# Multiplexers.net
KiCad netlist of a schematic drawn in Altium Designer
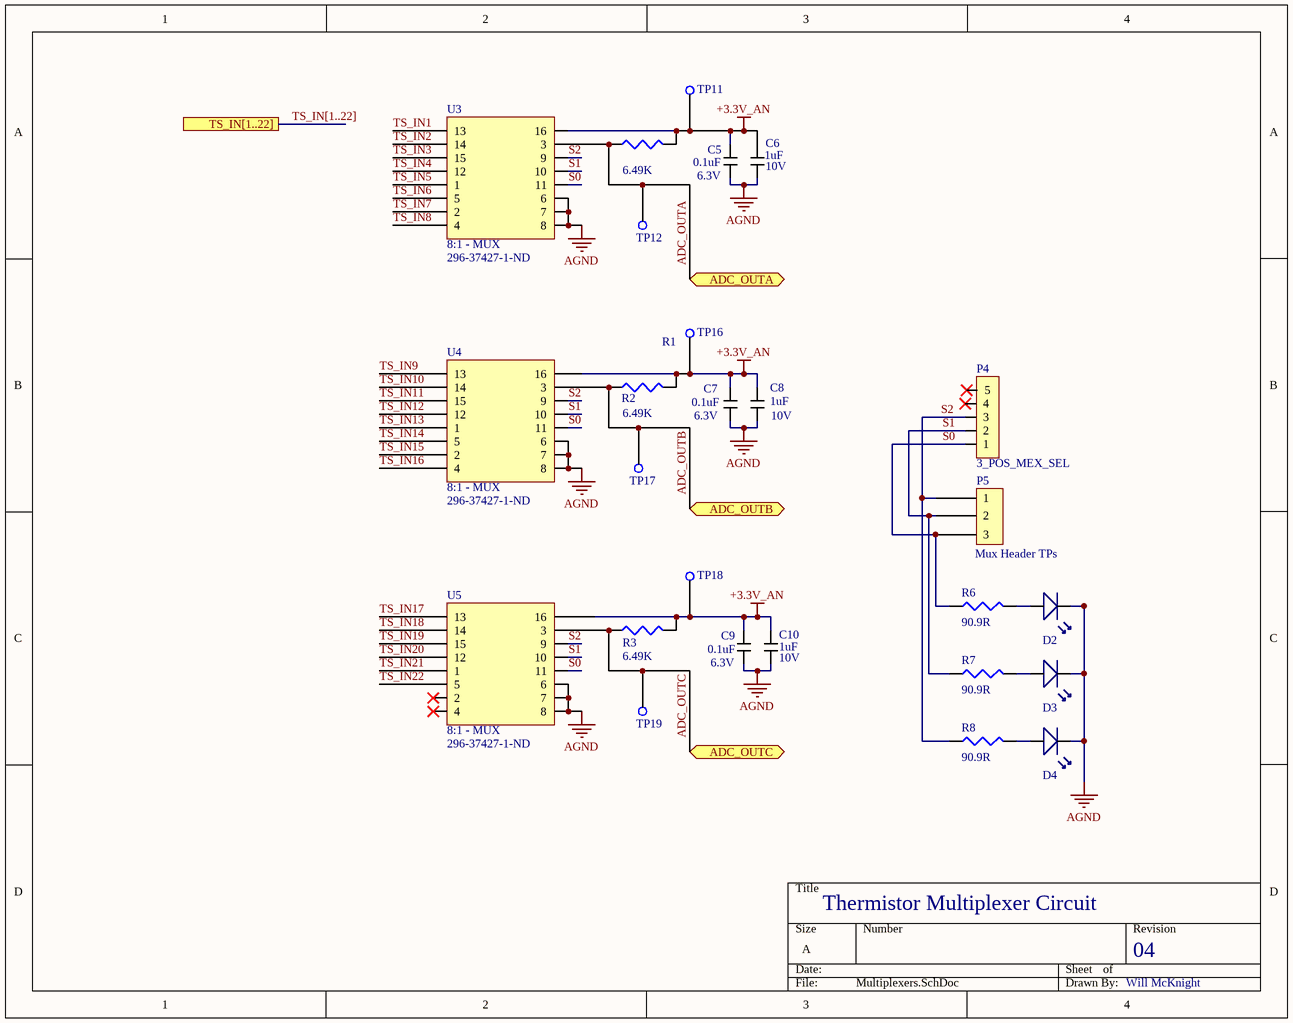
[diagram p0: Multiplexers.SchDoc]

(export (version "E")
  (design (tool "Eeschema 10.0.6"))
  (components
    (comp (ref "C5")
      (value "0.1uF")
      (footprint "0.1uF Bypass Capacitor")
      (description "0.1uF Bypass Cap")
      (fields
        (field (name "MANUFACTURER") "KEMET")
        (field (name "MANUFACTURER PART NUMBER") "C0603C104K9RACTU")
        (field (name "VOLTAGE RATING") "6.3V")
      )
      (libsource (lib "Schematic_Library") (part "0.1uF Cap"))
    )
    (comp (ref "C6")
      (value "1uF")
      (footprint "1UF_SAMSUNG")
      (description "1uF Samsung Cap")
      (fields
        (field (name "MANUFACTURER") "Samsung")
        (field (name "MANUFACTURER PART NUMBER") "CL10B105KP8NNNC")
        (field (name "CAPACITANCE") "1uF")
        (field (name "VOLTAGE RATING") "10V")
      )
      (libsource (lib "Schematic_Library") (part "1uF Samsung Cap"))
    )
    (comp (ref "C7")
      (value "0.1uF")
      (footprint "0.1uF Bypass Capacitor")
      (description "0.1uF Bypass Cap")
      (fields
        (field (name "MANUFACTURER") "KEMET")
        (field (name "MANUFACTURER PART NUMBER") "C0603C104K9RACTU")
        (field (name "VOLTAGE RATING") "6.3V")
      )
      (libsource (lib "Schematic_Library") (part "0.1uF Cap"))
    )
    (comp (ref "C8")
      (value "1uF")
      (footprint "1UF_SAMSUNG")
      (description "1uF Samsung Cap")
      (fields
        (field (name "MANUFACTURER") "Samsung")
        (field (name "MANUFACTURER PART NUMBER") "CL10B105KP8NNNC")
        (field (name "CAPACITANCE") "1uF")
        (field (name "VOLTAGE RATING") "10V")
      )
      (libsource (lib "Schematic_Library") (part "1uF Samsung Cap"))
    )
    (comp (ref "C9")
      (value "0.1uF")
      (footprint "0.1uF Bypass Capacitor")
      (description "0.1uF Bypass Cap")
      (fields
        (field (name "MANUFACTURER") "KEMET")
        (field (name "MANUFACTURER PART NUMBER") "C0603C104K9RACTU")
        (field (name "VOLTAGE RATING") "6.3V")
      )
      (libsource (lib "Schematic_Library") (part "0.1uF Cap"))
    )
    (comp (ref "C10")
      (value "1uF")
      (footprint "1UF_SAMSUNG")
      (description "1uF Samsung Cap")
      (fields
        (field (name "MANUFACTURER") "Samsung")
        (field (name "MANUFACTURER PART NUMBER") "CL10B105KP8NNNC")
        (field (name "CAPACITANCE") "1uF")
        (field (name "VOLTAGE RATING") "10V")
      )
      (libsource (lib "Schematic_Library") (part "1uF Samsung Cap"))
    )
    (comp (ref "D2")
      (value "LED")
      (footprint "Green_SMD_LED")
      (fields
        (field (name "MANUFACTURER") "Dialight")
        (field (name "MANUFACTURER PART NUMBER") "5988070107F")
      )
      (libsource (lib "Schematic_Library") (part "GREEN_LED"))
    )
    (comp (ref "D3")
      (value "LED")
      (footprint "Green_SMD_LED")
      (fields
        (field (name "MANUFACTURER") "Dialight")
        (field (name "MANUFACTURER PART NUMBER") "5988070107F")
      )
      (libsource (lib "Schematic_Library") (part "GREEN_LED"))
    )
    (comp (ref "D4")
      (value "LED")
      (footprint "Green_SMD_LED")
      (fields
        (field (name "MANUFACTURER") "Dialight")
        (field (name "MANUFACTURER PART NUMBER") "5988070107F")
      )
      (libsource (lib "Schematic_Library") (part "GREEN_LED"))
    )
    (comp (ref "P4")
      (value "3_POS_MEX_SEL")
      (footprint "3POS_MUX_SEL")
      (description "Connector Header Surface Mount, Right Angle 3 position 0.049\" (1.25mm)")
      (fields (field (name "MANUFACTURER") "Molex") (field (name "MANUFACTURER PART NUMBER") "505567-0371"))
      (libsource (lib "Schematic_Library") (part "3_POS_MEX_SEL"))
    )
    (comp (ref "P5")
      (value "3 POS Mux Select Header")
      (footprint "Mux Select 3 Pos Header Pin")
      (description "Mux Sel Header TP")
      (fields
        (field (name "MANUFACTURER") "Adam Equipment")
        (field (name "MANUFACTURER PART NUMBER") "PH1RA-03-UA")
      )
      (libsource (lib "Schematic_Library") (part "3 POS Mux Select Header"))
    )
    (comp (ref "R1")
      (value "6.49kOhm SMD Resistor")
      (footprint "RESC2012X06N")
      (fields
        (field (name "MANUFACTURER") "Panasonic")
        (field (name "MANUFACTURER PART NUMBER") "ERA6AEB6491V")
        (field (name "TOLERANCE") "0.1%")
        (field (name "RESISTANCE") "6.49K")
      )
      (libsource (lib "Schematic_Library") (part "6.49kOhm SMD Resistor"))
    )
    (comp (ref "R2")
      (value "6.49kOhm SMD Resistor")
      (footprint "RESC2012X06N")
      (fields
        (field (name "MANUFACTURER") "Panasonic")
        (field (name "MANUFACTURER PART NUMBER") "ERA6AEB6491V")
        (field (name "TOLERANCE") "0.1%")
        (field (name "RESISTANCE") "6.49K")
      )
      (libsource (lib "Schematic_Library") (part "6.49kOhm SMD Resistor"))
    )
    (comp (ref "R3")
      (value "6.49kOhm SMD Resistor")
      (footprint "RESC2012X06N")
      (fields
        (field (name "MANUFACTURER") "Panasonic")
        (field (name "MANUFACTURER PART NUMBER") "ERA6AEB6491V")
        (field (name "TOLERANCE") "0.1%")
        (field (name "RESISTANCE") "6.49K")
      )
      (libsource (lib "Schematic_Library") (part "6.49kOhm SMD Resistor"))
    )
    (comp (ref "R6")
      (value "Green_LED_Res")
      (footprint "Green_LED_Resistor_90.9")
      (fields
        (field (name "MANUFACTURER") "Panasonic")
        (field (name "MANUFACTURER PART NUMBER") "ERJ-1GNF90R9C")
        (field (name "TOLERANCE") "1%")
        (field (name "RESISTANCE") "90.9R")
      )
      (libsource (lib "Schematic_Library") (part "Green_LED_Res"))
    )
    (comp (ref "R7")
      (value "Green_LED_Res")
      (footprint "Green_LED_Resistor_90.9")
      (fields
        (field (name "MANUFACTURER") "Panasonic")
        (field (name "MANUFACTURER PART NUMBER") "ERJ-1GNF90R9C")
        (field (name "TOLERANCE") "1%")
        (field (name "RESISTANCE") "90.9R")
      )
      (libsource (lib "Schematic_Library") (part "Green_LED_Res"))
    )
    (comp (ref "R8")
      (value "Green_LED_Res")
      (footprint "Green_LED_Resistor_90.9")
      (fields
        (field (name "MANUFACTURER") "Panasonic")
        (field (name "MANUFACTURER PART NUMBER") "ERJ-1GNF90R9C")
        (field (name "TOLERANCE") "1%")
        (field (name "RESISTANCE") "90.9R")
      )
      (libsource (lib "Schematic_Library") (part "Green_LED_Res"))
    )
    (comp (ref "TP11")
      (value "Test Point")
      (footprint "Test Point")
      (libsource (lib "Schematic_Library") (part "Test Point"))
    )
    (comp (ref "TP12")
      (value "Test Point")
      (footprint "Test Point")
      (libsource (lib "Schematic_Library") (part "Test Point"))
    )
    (comp (ref "TP16")
      (value "Test Point")
      (footprint "Test Point")
      (libsource (lib "Schematic_Library") (part "Test Point"))
    )
    (comp (ref "TP17")
      (value "Test Point")
      (footprint "Test Point")
      (libsource (lib "Schematic_Library") (part "Test Point"))
    )
    (comp (ref "TP18")
      (value "Test Point")
      (footprint "Test Point")
      (libsource (lib "Schematic_Library") (part "Test Point"))
    )
    (comp (ref "TP19")
      (value "Test Point")
      (footprint "Test Point")
      (libsource (lib "Schematic_Library") (part "Test Point"))
    )
    (comp (ref "U3")
      (value "8:1 - MUX")
      (footprint "8x1 16SOIC MUX")
      (description "Current Therm 8:1 Mux")
      (fields
        (field (name "MANUFACTURER") "Texas Instruments")
        (field (name "MANUFACTURER PART NUMBER") "SN74LV4051ATPWRQ1")
        (field (name "SUPPLIER PART NUMBER 1") "296-37427-1-ND")
      )
      (libsource (lib "Schematic_Library") (part "8{colon}1 - MUX"))
    )
    (comp (ref "U4")
      (value "8:1 - MUX")
      (footprint "8x1 16SOIC MUX")
      (description "Current Therm 8:1 Mux")
      (fields
        (field (name "MANUFACTURER") "Texas Instruments")
        (field (name "MANUFACTURER PART NUMBER") "SN74LV4051ATPWRQ1")
        (field (name "SUPPLIER PART NUMBER 1") "296-37427-1-ND")
      )
      (libsource (lib "Schematic_Library") (part "8{colon}1 - MUX"))
    )
    (comp (ref "U5")
      (value "8:1 - MUX")
      (footprint "8x1 16SOIC MUX")
      (description "Current Therm 8:1 Mux")
      (fields
        (field (name "MANUFACTURER") "Texas Instruments")
        (field (name "MANUFACTURER PART NUMBER") "SN74LV4051ATPWRQ1")
        (field (name "SUPPLIER PART NUMBER 1") "296-37427-1-ND")
      )
      (libsource (lib "Schematic_Library") (part "8{colon}1 - MUX"))
    )
  )
  (nets
    (net (code "1") (name "+3.3V_AN") (class "Default")
      (node (ref "C10") (pin "2") (pinfunction "2_2") (pintype "passive"))
      (node (ref "C5") (pin "2") (pinfunction "2_2") (pintype "passive"))
      (node (ref "C6") (pin "2") (pinfunction "2_2") (pintype "passive"))
      (node (ref "C7") (pin "2") (pinfunction "2_2") (pintype "passive"))
      (node (ref "C8") (pin "2") (pinfunction "2_2") (pintype "passive"))
      (node (ref "C9") (pin "2") (pinfunction "2_2") (pintype "passive"))
      (node (ref "R1") (pin "2") (pinfunction "2_2") (pintype "passive"))
      (node (ref "R2") (pin "2") (pinfunction "2_2") (pintype "passive"))
      (node (ref "R3") (pin "2") (pinfunction "2_2") (pintype "passive"))
      (node (ref "TP11") (pin "1") (pinfunction "1_1") (pintype "passive"))
      (node (ref "TP16") (pin "1") (pinfunction "1_1") (pintype "passive"))
      (node (ref "TP18") (pin "1") (pinfunction "1_1") (pintype "passive"))
      (node (ref "U3") (pin "16") (pinfunction "16_16") (pintype "passive"))
      (node (ref "U4") (pin "16") (pinfunction "16_16") (pintype "passive"))
      (node (ref "U5") (pin "16") (pinfunction "16_16") (pintype "passive"))
    )
    (net (code "2") (name "/ADC_OUTA") (class "Default")
      (node (ref "R1") (pin "1") (pinfunction "1_1") (pintype "passive"))
      (node (ref "TP12") (pin "1") (pinfunction "1_1") (pintype "passive"))
      (node (ref "U3") (pin "3") (pinfunction "3_3") (pintype "passive"))
    )
    (net (code "3") (name "/ADC_OUTB") (class "Default")
      (node (ref "R2") (pin "1") (pinfunction "1_1") (pintype "passive"))
      (node (ref "TP17") (pin "1") (pinfunction "1_1") (pintype "passive"))
      (node (ref "U4") (pin "3") (pinfunction "3_3") (pintype "passive"))
    )
    (net (code "4") (name "/ADC_OUTC") (class "Default")
      (node (ref "R3") (pin "1") (pinfunction "1_1") (pintype "passive"))
      (node (ref "TP19") (pin "1") (pinfunction "1_1") (pintype "passive"))
      (node (ref "U5") (pin "3") (pinfunction "3_3") (pintype "passive"))
    )
    (net (code "5") (name "/S0") (class "Default")
      (node (ref "P4") (pin "1") (pinfunction "1_1") (pintype "passive"))
      (node (ref "P5") (pin "3") (pinfunction "3_3") (pintype "passive"))
      (node (ref "R6") (pin "1") (pinfunction "1_1") (pintype "passive"))
      (node (ref "U3") (pin "11") (pinfunction "11_11") (pintype "passive"))
      (node (ref "U4") (pin "11") (pinfunction "11_11") (pintype "passive"))
      (node (ref "U5") (pin "11") (pinfunction "11_11") (pintype "passive"))
    )
    (net (code "6") (name "/S1") (class "Default")
      (node (ref "P4") (pin "2") (pinfunction "2_2") (pintype "passive"))
      (node (ref "P5") (pin "2") (pinfunction "2_2") (pintype "passive"))
      (node (ref "R7") (pin "1") (pinfunction "1_1") (pintype "passive"))
      (node (ref "U3") (pin "10") (pinfunction "10_10") (pintype "passive"))
      (node (ref "U4") (pin "10") (pinfunction "10_10") (pintype "passive"))
      (node (ref "U5") (pin "10") (pinfunction "10_10") (pintype "passive"))
    )
    (net (code "7") (name "/S2") (class "Default")
      (node (ref "P4") (pin "3") (pinfunction "3_3") (pintype "passive"))
      (node (ref "P5") (pin "1") (pinfunction "1_1") (pintype "passive"))
      (node (ref "R8") (pin "1") (pinfunction "1_1") (pintype "passive"))
      (node (ref "U3") (pin "9") (pinfunction "9_9") (pintype "passive"))
      (node (ref "U4") (pin "9") (pinfunction "9_9") (pintype "passive"))
      (node (ref "U5") (pin "9") (pinfunction "9_9") (pintype "passive"))
    )
    (net (code "8") (name "/TS_IN1") (class "Default")
      (node (ref "U3") (pin "13") (pinfunction "13_13") (pintype "passive"))
    )
    (net (code "9") (name "/TS_IN2") (class "Default")
      (node (ref "U3") (pin "14") (pinfunction "14_14") (pintype "passive"))
    )
    (net (code "10") (name "/TS_IN3") (class "Default")
      (node (ref "U3") (pin "15") (pinfunction "15_15") (pintype "passive"))
    )
    (net (code "11") (name "/TS_IN4") (class "Default")
      (node (ref "U3") (pin "12") (pinfunction "12_12") (pintype "passive"))
    )
    (net (code "12") (name "/TS_IN5") (class "Default")
      (node (ref "U3") (pin "1") (pinfunction "1_1") (pintype "passive"))
    )
    (net (code "13") (name "/TS_IN6") (class "Default")
      (node (ref "U3") (pin "5") (pinfunction "5_5") (pintype "passive"))
    )
    (net (code "14") (name "/TS_IN7") (class "Default")
      (node (ref "U3") (pin "2") (pinfunction "2_2") (pintype "passive"))
    )
    (net (code "15") (name "/TS_IN8") (class "Default")
      (node (ref "U3") (pin "4") (pinfunction "4_4") (pintype "passive"))
    )
    (net (code "16") (name "/TS_IN9") (class "Default")
      (node (ref "U4") (pin "13") (pinfunction "13_13") (pintype "passive"))
    )
    (net (code "17") (name "/TS_IN10") (class "Default")
      (node (ref "U4") (pin "14") (pinfunction "14_14") (pintype "passive"))
    )
    (net (code "18") (name "/TS_IN11") (class "Default")
      (node (ref "U4") (pin "15") (pinfunction "15_15") (pintype "passive"))
    )
    (net (code "19") (name "/TS_IN12") (class "Default")
      (node (ref "U4") (pin "12") (pinfunction "12_12") (pintype "passive"))
    )
    (net (code "20") (name "/TS_IN13") (class "Default")
      (node (ref "U4") (pin "1") (pinfunction "1_1") (pintype "passive"))
    )
    (net (code "21") (name "/TS_IN14") (class "Default")
      (node (ref "U4") (pin "5") (pinfunction "5_5") (pintype "passive"))
    )
    (net (code "22") (name "/TS_IN15") (class "Default")
      (node (ref "U4") (pin "2") (pinfunction "2_2") (pintype "passive"))
    )
    (net (code "23") (name "/TS_IN16") (class "Default")
      (node (ref "U4") (pin "4") (pinfunction "4_4") (pintype "passive"))
    )
    (net (code "24") (name "/TS_IN17") (class "Default")
      (node (ref "U5") (pin "13") (pinfunction "13_13") (pintype "passive"))
    )
    (net (code "25") (name "/TS_IN18") (class "Default")
      (node (ref "U5") (pin "14") (pinfunction "14_14") (pintype "passive"))
    )
    (net (code "26") (name "/TS_IN19") (class "Default")
      (node (ref "U5") (pin "15") (pinfunction "15_15") (pintype "passive"))
    )
    (net (code "27") (name "/TS_IN20") (class "Default")
      (node (ref "U5") (pin "12") (pinfunction "12_12") (pintype "passive"))
    )
    (net (code "28") (name "/TS_IN21") (class "Default")
      (node (ref "U5") (pin "1") (pinfunction "1_1") (pintype "passive"))
    )
    (net (code "29") (name "/TS_IN22") (class "Default")
      (node (ref "U5") (pin "5") (pinfunction "5_5") (pintype "passive"))
    )
    (net (code "31") (name "AGND") (class "Default")
      (node (ref "C10") (pin "1") (pinfunction "1_1") (pintype "passive"))
      (node (ref "C5") (pin "1") (pinfunction "1_1") (pintype "passive"))
      (node (ref "C6") (pin "1") (pinfunction "1_1") (pintype "passive"))
      (node (ref "C7") (pin "1") (pinfunction "1_1") (pintype "passive"))
      (node (ref "C8") (pin "1") (pinfunction "1_1") (pintype "passive"))
      (node (ref "C9") (pin "1") (pinfunction "1_1") (pintype "passive"))
      (node (ref "D2") (pin "1") (pinfunction "1_1") (pintype "passive"))
      (node (ref "D3") (pin "1") (pinfunction "1_1") (pintype "passive"))
      (node (ref "D4") (pin "1") (pinfunction "1_1") (pintype "passive"))
      (node (ref "U3") (pin "6") (pinfunction "6_6") (pintype "passive"))
      (node (ref "U3") (pin "7") (pinfunction "7_7") (pintype "passive"))
      (node (ref "U3") (pin "8") (pinfunction "8_8") (pintype "passive"))
      (node (ref "U4") (pin "6") (pinfunction "6_6") (pintype "passive"))
      (node (ref "U4") (pin "7") (pinfunction "7_7") (pintype "passive"))
      (node (ref "U4") (pin "8") (pinfunction "8_8") (pintype "passive"))
      (node (ref "U5") (pin "6") (pinfunction "6_6") (pintype "passive"))
      (node (ref "U5") (pin "7") (pinfunction "7_7") (pintype "passive"))
      (node (ref "U5") (pin "8") (pinfunction "8_8") (pintype "passive"))
    )
    (net (code "32") (name "Net-(D2-Pad2)") (class "Default")
      (node (ref "D2") (pin "2") (pinfunction "2_2") (pintype "passive"))
      (node (ref "R6") (pin "2") (pinfunction "2_2") (pintype "passive"))
    )
    (net (code "33") (name "Net-(D3-Pad2)") (class "Default")
      (node (ref "D3") (pin "2") (pinfunction "2_2") (pintype "passive"))
      (node (ref "R7") (pin "2") (pinfunction "2_2") (pintype "passive"))
    )
    (net (code "34") (name "Net-(D4-Pad2)") (class "Default")
      (node (ref "D4") (pin "2") (pinfunction "2_2") (pintype "passive"))
      (node (ref "R8") (pin "2") (pinfunction "2_2") (pintype "passive"))
    )
    (net (code "35") (name "unconnected-(P4-Pad4)") (class "Default")
      (node (ref "P4") (pin "4") (pinfunction "4_4") (pintype "passive+no_connect"))
    )
    (net (code "36") (name "unconnected-(P4-Pad5)") (class "Default")
      (node (ref "P4") (pin "5") (pinfunction "5_5") (pintype "passive+no_connect"))
    )
    (net (code "37") (name "unconnected-(U5-Pad2)") (class "Default")
      (node (ref "U5") (pin "2") (pinfunction "2_2") (pintype "passive+no_connect"))
    )
    (net (code "38") (name "unconnected-(U5-Pad4)") (class "Default")
      (node (ref "U5") (pin "4") (pinfunction "4_4") (pintype "passive+no_connect"))
    )
  )
)
